# clapclap2313.net
KiCad netlist of a schematic drawn in EAGLE
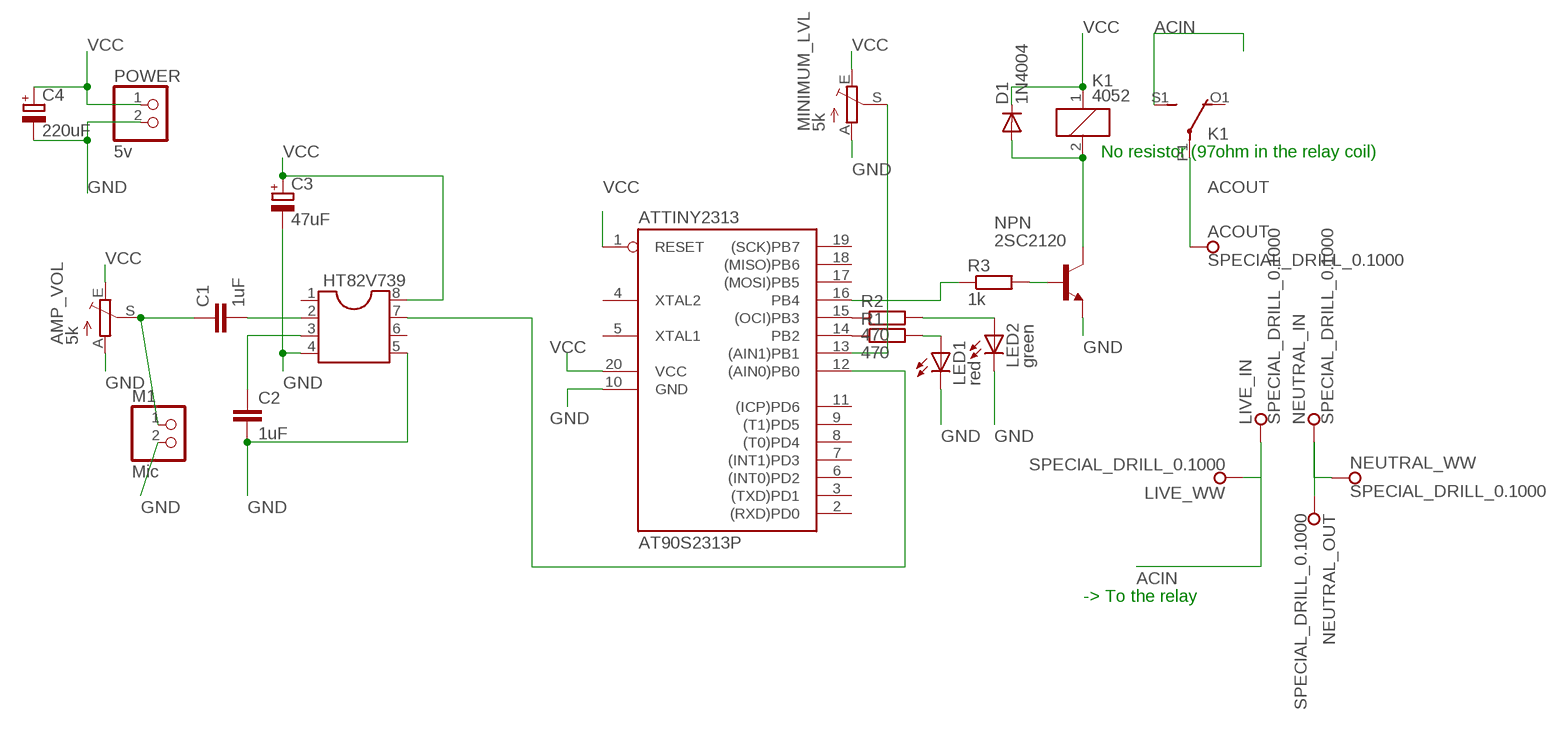
[diagram p0: schematic, sheet 1]

(export (version "E")
  (design (tool "Eeschema 10.0.6"))
  (components
    (comp (ref "ACOUT")
      (value "SPECIAL_DRILL_0.1000")
      (footprint "eagle-import:PAD_0.1000")
      (libsource (lib "eagle-import") (part "SPECIAL_DRILL_0.1000"))
    )
    (comp (ref "AMP_VOL")
      (value "5k")
      (footprint "eagle-import:CT6")
      (libsource (lib "eagle-import") (part "TRIM_EU-CT6"))
    )
    (comp (ref "ATTINY2313")
      (value "AT90S2313P")
      (footprint "eagle-import:DIL20")
      (libsource (lib "eagle-import") (part "AT90S2313P"))
    )
    (comp (ref "C1")
      (value "1uF")
      (footprint "eagle-import:C050-024X044")
      (libsource (lib "eagle-import") (part "C-EU050-024X044"))
    )
    (comp (ref "C2")
      (value "1uF")
      (footprint "eagle-import:C050-024X044")
      (libsource (lib "eagle-import") (part "C-EU050-024X044"))
    )
    (comp (ref "C3")
      (value "47uF")
      (footprint "eagle-import:E2,5-6")
      (libsource (lib "eagle-import") (part "resistor_CPOL-EUE2.5-6"))
    )
    (comp (ref "C4")
      (value "220uF")
      (footprint "eagle-import:E2,5-6E")
      (libsource (lib "eagle-import") (part "CPOL-EUE2,5-6E"))
    )
    (comp (ref "D1")
      (value "1N4004")
      (footprint "eagle-import:DO41-10")
      (libsource (lib "eagle-import") (part "1N4004"))
    )
    (comp (ref "HT82V739")
      (value "DIL8S")
      (footprint "eagle-import:SOCKET-08")
      (libsource (lib "eagle-import") (part "DIL8S"))
    )
    (comp (ref "K1")
      (value "4052")
      (footprint "eagle-import:F4052")
      (libsource (lib "eagle-import") (part "4052"))
    )
    (comp (ref "LED1")
      (value "red")
      (footprint "eagle-import:LED3MM")
      (libsource (lib "eagle-import") (part "LED3MM"))
    )
    (comp (ref "LED2")
      (value "green")
      (footprint "eagle-import:LED3MM")
      (libsource (lib "eagle-import") (part "LED3MM"))
    )
    (comp (ref "LIVE_IN")
      (value "SPECIAL_DRILL_0.1000")
      (footprint "eagle-import:PAD_0.1000")
      (libsource (lib "eagle-import") (part "SPECIAL_DRILL_0.1000"))
    )
    (comp (ref "LIVE_WW")
      (value "SPECIAL_DRILL_0.1000")
      (footprint "eagle-import:PAD_0.1000")
      (libsource (lib "eagle-import") (part "SPECIAL_DRILL_0.1000"))
    )
    (comp (ref "M1")
      (value "Mic")
      (footprint "eagle-import:1X02")
      (libsource (lib "eagle-import") (part "PINHD-1X2"))
    )
    (comp (ref "MINIMUM_LVL")
      (value "5k")
      (footprint "eagle-import:CT6")
      (libsource (lib "eagle-import") (part "TRIM_EU-CT6"))
    )
    (comp (ref "NEUTRAL_IN")
      (value "SPECIAL_DRILL_0.1000")
      (footprint "eagle-import:PAD_0.1000")
      (libsource (lib "eagle-import") (part "SPECIAL_DRILL_0.1000"))
    )
    (comp (ref "NEUTRAL_OUT")
      (value "SPECIAL_DRILL_0.1000")
      (footprint "eagle-import:PAD_0.1000")
      (libsource (lib "eagle-import") (part "SPECIAL_DRILL_0.1000"))
    )
    (comp (ref "NEUTRAL_WW")
      (value "SPECIAL_DRILL_0.1000")
      (footprint "eagle-import:PAD_0.1000")
      (libsource (lib "eagle-import") (part "SPECIAL_DRILL_0.1000"))
    )
    (comp (ref "NPN")
      (value "2SC2120")
      (footprint "eagle-import:TO92-ECB")
      (libsource (lib "eagle-import") (part "-NPN-TO92-ECB"))
    )
    (comp (ref "POWER")
      (value "5v")
      (footprint "eagle-import:1X02")
      (libsource (lib "eagle-import") (part "PINHD-1X2"))
    )
    (comp (ref "R1")
      (value "470")
      (footprint "eagle-import:0204V")
      (libsource (lib "eagle-import") (part "R-EU_0204/2V"))
    )
    (comp (ref "R2")
      (value "470")
      (footprint "eagle-import:0204V")
      (libsource (lib "eagle-import") (part "R-EU_0204/2V"))
    )
    (comp (ref "R3")
      (value "1k")
      (footprint "eagle-import:0207_2V")
      (libsource (lib "eagle-import") (part "R-EU_0207/2V"))
    )
  )
  (nets
    (net (code "1") (name "/ACIN") (class "Default")
      (node (ref "K1") (pin "S1") (pinfunction "S_S1") (pintype "passive"))
      (node (ref "LIVE_IN") (pin "1") (pinfunction "1_1") (pintype "passive"))
      (node (ref "LIVE_WW") (pin "1") (pinfunction "1_1") (pintype "passive"))
    )
    (net (code "2") (name "/ACOUT") (class "Default")
      (node (ref "ACOUT") (pin "1") (pinfunction "1_1") (pintype "passive"))
      (node (ref "K1") (pin "P1") (pinfunction "P_P1") (pintype "passive"))
    )
    (net (code "3") (name "/GND") (class "Default")
      (node (ref "AMP_VOL") (pin "A") (pinfunction "A_A") (pintype "passive"))
      (node (ref "ATTINY2313") (pin "10") (pinfunction "GND_10") (pintype "power_in"))
      (node (ref "C2") (pin "2") (pinfunction "2_2") (pintype "passive"))
      (node (ref "C3") (pin "-") (pinfunction "-_-") (pintype "passive"))
      (node (ref "C4") (pin "-") (pinfunction "-_-") (pintype "passive"))
      (node (ref "HT82V739") (pin "4") (pinfunction "4_4") (pintype "passive"))
      (node (ref "HT82V739") (pin "5") (pinfunction "5_5") (pintype "passive"))
      (node (ref "LED1") (pin "K") (pinfunction "C_K") (pintype "passive"))
      (node (ref "LED2") (pin "K") (pinfunction "C_K") (pintype "passive"))
      (node (ref "M1") (pin "2") (pinfunction "2_2") (pintype "passive"))
      (node (ref "MINIMUM_LVL") (pin "A") (pinfunction "A_A") (pintype "passive"))
      (node (ref "NPN") (pin "E") (pinfunction "E_E") (pintype "passive"))
      (node (ref "POWER") (pin "2") (pinfunction "2_2") (pintype "passive"))
    )
    (net (code "4") (name "/VCC") (class "Default")
      (node (ref "AMP_VOL") (pin "E") (pinfunction "E_E") (pintype "passive"))
      (node (ref "ATTINY2313") (pin "1") (pinfunction "RESET_1") (pintype "bidirectional"))
      (node (ref "ATTINY2313") (pin "20") (pinfunction "VCC_20") (pintype "power_in"))
      (node (ref "C3") (pin "+") (pinfunction "+_+") (pintype "passive"))
      (node (ref "C4") (pin "+") (pinfunction "+_+") (pintype "passive"))
      (node (ref "D1") (pin "C") (pinfunction "C_C") (pintype "passive"))
      (node (ref "HT82V739") (pin "8") (pinfunction "8_8") (pintype "passive"))
      (node (ref "K1") (pin "1") (pinfunction "1_1") (pintype "passive"))
      (node (ref "MINIMUM_LVL") (pin "E") (pinfunction "E_E") (pintype "passive"))
      (node (ref "POWER") (pin "1") (pinfunction "1_1") (pintype "passive"))
    )
    (net (code "5") (name "Net-(AMP_VOL-PadS)") (class "Default")
      (node (ref "AMP_VOL") (pin "S") (pinfunction "S_S") (pintype "passive"))
      (node (ref "C1") (pin "1") (pinfunction "1_1") (pintype "passive"))
      (node (ref "M1") (pin "1") (pinfunction "1_1") (pintype "passive"))
    )
    (net (code "6") (name "Net-(ATTINY2313-(AIN0)PB0)") (class "Default")
      (node (ref "ATTINY2313") (pin "12") (pinfunction "(AIN0)PB0_12") (pintype "bidirectional"))
      (node (ref "HT82V739") (pin "7") (pinfunction "7_7") (pintype "passive"))
    )
    (net (code "7") (name "Net-(ATTINY2313-(AIN1)PB1)") (class "Default")
      (node (ref "ATTINY2313") (pin "13") (pinfunction "(AIN1)PB1_13") (pintype "bidirectional"))
      (node (ref "MINIMUM_LVL") (pin "S") (pinfunction "S_S") (pintype "passive"))
    )
    (net (code "8") (name "Net-(ATTINY2313-(OCI)PB3)") (class "Default")
      (node (ref "ATTINY2313") (pin "15") (pinfunction "(OCI)PB3_15") (pintype "bidirectional"))
      (node (ref "R2") (pin "1") (pinfunction "1_1") (pintype "passive"))
    )
    (net (code "9") (name "Net-(ATTINY2313-PB2)") (class "Default")
      (node (ref "ATTINY2313") (pin "14") (pinfunction "PB2_14") (pintype "bidirectional"))
      (node (ref "R1") (pin "1") (pinfunction "1_1") (pintype "passive"))
    )
    (net (code "10") (name "Net-(ATTINY2313-PB4)") (class "Default")
      (node (ref "ATTINY2313") (pin "16") (pinfunction "PB4_16") (pintype "bidirectional"))
      (node (ref "R3") (pin "1") (pinfunction "1_1") (pintype "passive"))
    )
    (net (code "11") (name "Net-(C1-Pad2)") (class "Default")
      (node (ref "C1") (pin "2") (pinfunction "2_2") (pintype "passive"))
      (node (ref "HT82V739") (pin "2") (pinfunction "2_2") (pintype "passive"))
    )
    (net (code "12") (name "Net-(C2-Pad1)") (class "Default")
      (node (ref "C2") (pin "1") (pinfunction "1_1") (pintype "passive"))
      (node (ref "HT82V739") (pin "3") (pinfunction "3_3") (pintype "passive"))
    )
    (net (code "13") (name "Net-(D1-PadA)") (class "Default")
      (node (ref "D1") (pin "A") (pinfunction "A_A") (pintype "passive"))
      (node (ref "K1") (pin "2") (pinfunction "2_2") (pintype "passive"))
      (node (ref "NPN") (pin "C") (pinfunction "C_C") (pintype "passive"))
    )
    (net (code "14") (name "Net-(LED1-PadA)") (class "Default")
      (node (ref "LED1") (pin "A") (pinfunction "A_A") (pintype "passive"))
      (node (ref "R1") (pin "2") (pinfunction "2_2") (pintype "passive"))
    )
    (net (code "15") (name "Net-(LED2-PadA)") (class "Default")
      (node (ref "LED2") (pin "A") (pinfunction "A_A") (pintype "passive"))
      (node (ref "R2") (pin "2") (pinfunction "2_2") (pintype "passive"))
    )
    (net (code "16") (name "Net-(NEUTRAL_IN-Pad1)") (class "Default")
      (node (ref "NEUTRAL_IN") (pin "1") (pinfunction "1_1") (pintype "passive"))
      (node (ref "NEUTRAL_OUT") (pin "1") (pinfunction "1_1") (pintype "passive"))
      (node (ref "NEUTRAL_WW") (pin "1") (pinfunction "1_1") (pintype "passive"))
    )
    (net (code "17") (name "Net-(NPN-PadB)") (class "Default")
      (node (ref "NPN") (pin "B") (pinfunction "B_B") (pintype "passive"))
      (node (ref "R3") (pin "2") (pinfunction "2_2") (pintype "passive"))
    )
    (net (code "18") (name "unconnected-(ATTINY2313-(ICP)PD6-Pad11)") (class "Default")
      (node (ref "ATTINY2313") (pin "11") (pinfunction "(ICP)PD6_11") (pintype "bidirectional"))
    )
    (net (code "19") (name "unconnected-(ATTINY2313-(INT0)PD2-Pad6)") (class "Default")
      (node (ref "ATTINY2313") (pin "6") (pinfunction "(INT0)PD2_6") (pintype "bidirectional"))
    )
    (net (code "20") (name "unconnected-(ATTINY2313-(INT1)PD3-Pad7)") (class "Default")
      (node (ref "ATTINY2313") (pin "7") (pinfunction "(INT1)PD3_7") (pintype "bidirectional"))
    )
    (net (code "21") (name "unconnected-(ATTINY2313-(MISO)PB6-Pad18)") (class "Default")
      (node (ref "ATTINY2313") (pin "18") (pinfunction "(MISO)PB6_18") (pintype "bidirectional"))
    )
    (net (code "22") (name "unconnected-(ATTINY2313-(MOSI)PB5-Pad17)") (class "Default")
      (node (ref "ATTINY2313") (pin "17") (pinfunction "(MOSI)PB5_17") (pintype "bidirectional"))
    )
    (net (code "23") (name "unconnected-(ATTINY2313-(RXD)PD0-Pad2)") (class "Default")
      (node (ref "ATTINY2313") (pin "2") (pinfunction "(RXD)PD0_2") (pintype "bidirectional"))
    )
    (net (code "24") (name "unconnected-(ATTINY2313-(SCK)PB7-Pad19)") (class "Default")
      (node (ref "ATTINY2313") (pin "19") (pinfunction "(SCK)PB7_19") (pintype "bidirectional"))
    )
    (net (code "25") (name "unconnected-(ATTINY2313-(T0)PD4-Pad8)") (class "Default")
      (node (ref "ATTINY2313") (pin "8") (pinfunction "(T0)PD4_8") (pintype "bidirectional"))
    )
    (net (code "26") (name "unconnected-(ATTINY2313-(T1)PD5-Pad9)") (class "Default")
      (node (ref "ATTINY2313") (pin "9") (pinfunction "(T1)PD5_9") (pintype "bidirectional"))
    )
    (net (code "27") (name "unconnected-(ATTINY2313-(TXD)PD1-Pad3)") (class "Default")
      (node (ref "ATTINY2313") (pin "3") (pinfunction "(TXD)PD1_3") (pintype "bidirectional"))
    )
    (net (code "28") (name "unconnected-(ATTINY2313-XTAL1-Pad5)") (class "Default")
      (node (ref "ATTINY2313") (pin "5") (pinfunction "XTAL1_5") (pintype "bidirectional"))
    )
    (net (code "29") (name "unconnected-(ATTINY2313-XTAL2-Pad4)") (class "Default")
      (node (ref "ATTINY2313") (pin "4") (pinfunction "XTAL2_4") (pintype "bidirectional"))
    )
    (net (code "30") (name "unconnected-(HT82V739-Pad1)") (class "Default")
      (node (ref "HT82V739") (pin "1") (pinfunction "1_1") (pintype "passive"))
    )
    (net (code "31") (name "unconnected-(HT82V739-Pad6)") (class "Default")
      (node (ref "HT82V739") (pin "6") (pinfunction "6_6") (pintype "passive"))
    )
    (net (code "32") (name "unconnected-(K1B-O-PadO1)") (class "Default")
      (node (ref "K1") (pin "O1") (pinfunction "O_O1") (pintype "passive"))
    )
  )
)
